# Top.net
KiCad netlist of a schematic drawn in Altium Designer
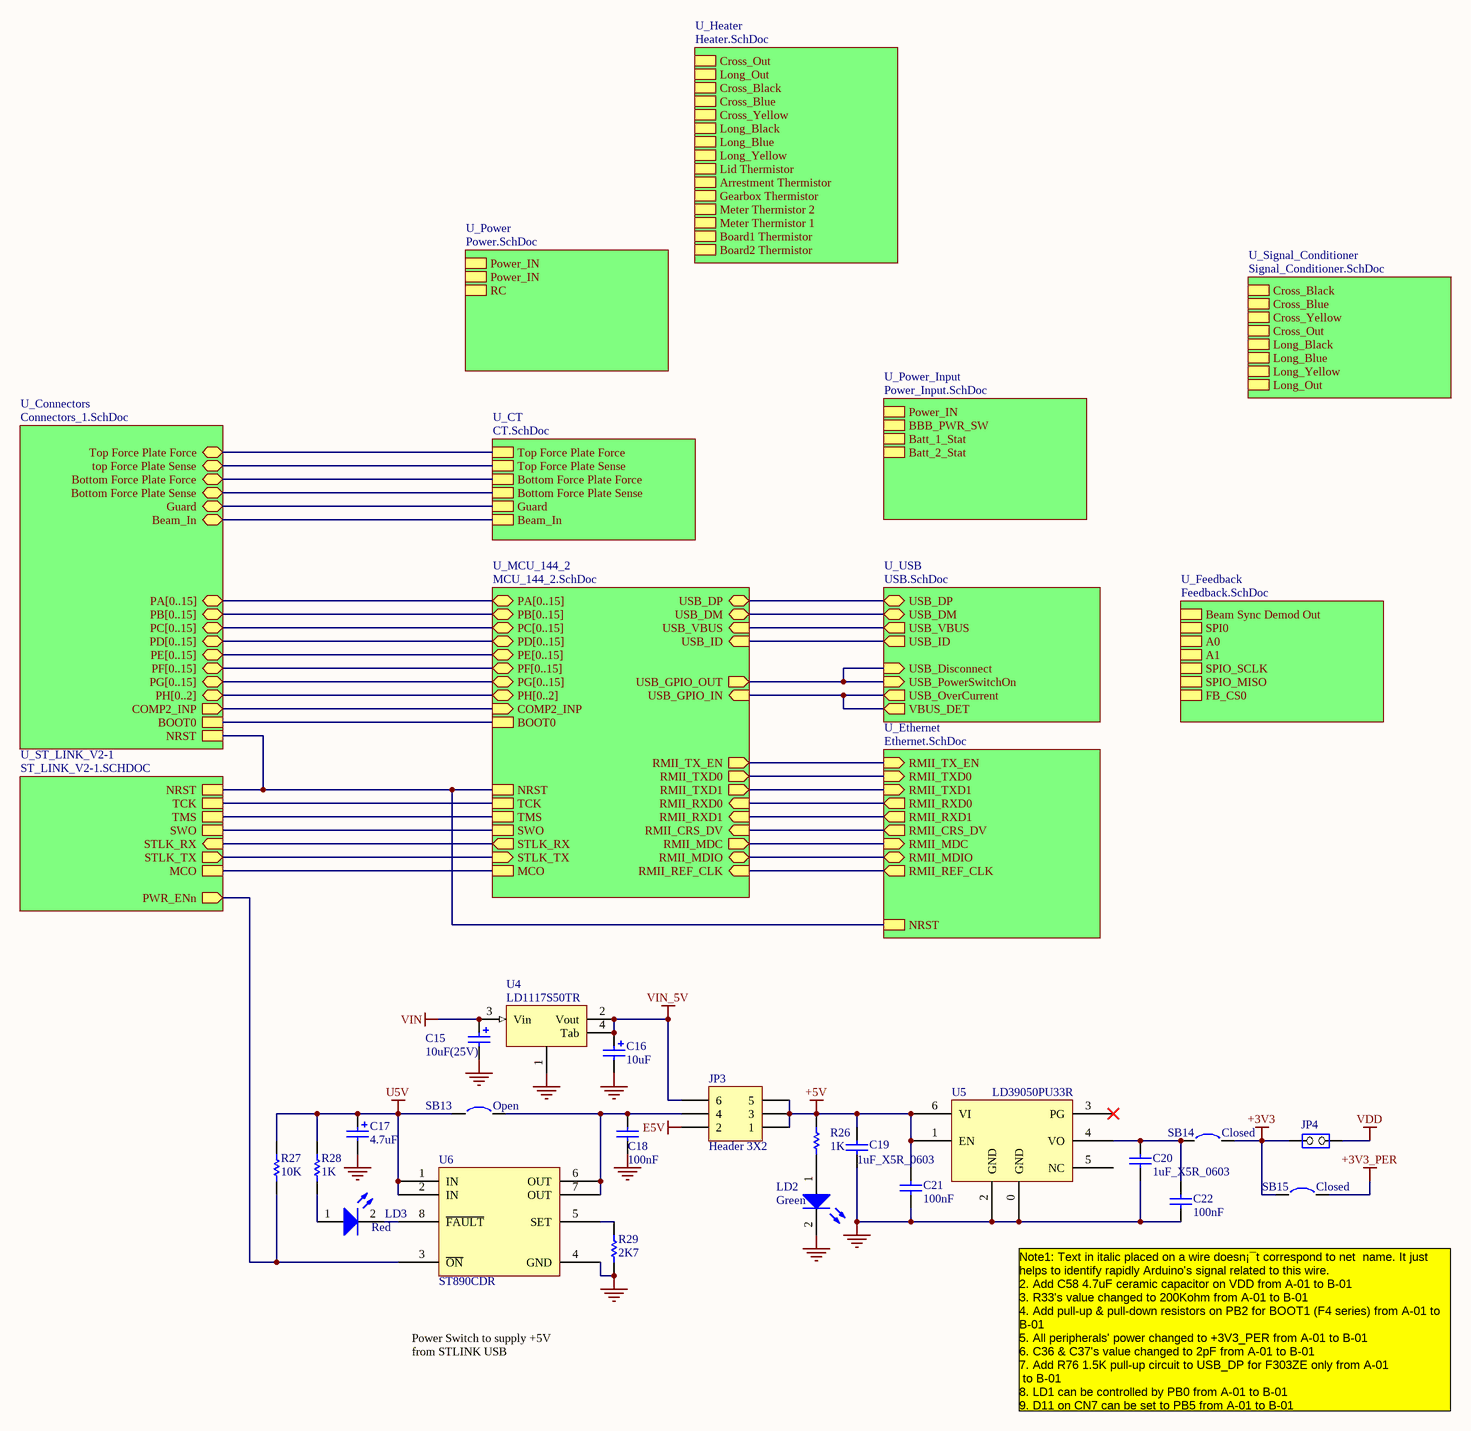
[diagram p0: Top.SchDoc]

(export (version "E")
  (design (tool "Eeschema 10.0.6"))
  (components
    (comp (ref "C15")
      (value "10uF(25V)")
      (footprint "TAN-B")
      (description "Polarized Capacitor (Radial)")
      (fields (field (name "PUBLISHER") "Altium Limited"))
      (libsource (lib "Miscellaneous Devices") (part "Cap Pol1"))
    )
    (comp (ref "C16")
      (value "10uF")
      (footprint "TAN-A")
      (description "Polarized Capacitor (Radial)")
      (fields (field (name "PUBLISHER") "Altium Limited"))
      (libsource (lib "Miscellaneous Devices") (part "Cap Pol1"))
    )
    (comp (ref "C17")
      (value "4.7uF")
      (footprint "TAN-A")
      (description "Polarized Capacitor (Radial)")
      (fields (field (name "PUBLISHER") "Altium Limited"))
      (libsource (lib "*") (part "Cap Pol1"))
    )
    (comp (ref "C18")
      (value "100nF")
      (footprint "0603C")
      (description "Capacitor 0402 / 0603 / 0805")
      (libsource (lib "MCD_TOOLS") (part "Capacitor_ST"))
    )
    (comp (ref "C19")
      (value "1uF_X5R_0603")
      (footprint "0603C")
      (description "0603  X5R 1µF")
      (fields (field (name "TOLERANCE") "10%"))
      (libsource (lib "MB963_1") (part "CAP SMD 0603  X5R 1µF 25V 10%"))
    )
    (comp (ref "C20")
      (value "1uF_X5R_0603")
      (footprint "0603C")
      (description "0603  X5R 1µF")
      (fields (field (name "TOLERANCE") "10%"))
      (libsource (lib "MB963_1") (part "CAP SMD 0603  X5R 1µF 25V 10%"))
    )
    (comp (ref "C21")
      (value "100nF")
      (footprint "0603C")
      (description "Capacitor 0402 / 0603 / 0805")
      (libsource (lib "MCD_TOOLS") (part "Capacitor_ST"))
    )
    (comp (ref "C22")
      (value "100nF")
      (footprint "0603C")
      (description "Capacitor 0402 / 0603 / 0805")
      (libsource (lib "MCD_TOOLS") (part "Capacitor_ST"))
    )
    (comp (ref "JP3")
      (value "Header 3X2")
      (footprint "HDR_3x2_2R54_V_M")
      (description "Header, 3-Pin, Dual row")
      (fields (field (name "PUBLISHER") "Altium Limited"))
      (libsource (lib "Miscellaneous Connectors") (part "Header 3X2"))
    )
    (comp (ref "JP4") (value "~") (footprint "HDR_1x2_2R54_V_M_S") (libsource (lib "*") (part "JP2")))
    (comp (ref "LD2")
      (value "Green")
      (footprint "0603D-G")
      (description "Typical RED, GREEN, YELLOW, AMBER GaAs LED")
      (fields (field (name "PUBLISHER") "Altium Limited"))
      (libsource (lib "") (part "LED2_1"))
    )
    (comp (ref "LD3")
      (value "Red")
      (footprint "0603D-R")
      (description "Typical RED, GREEN, YELLOW, AMBER GaAs LED")
      (fields (field (name "PUBLISHER") "Altium Limited"))
      (libsource (lib "Miscellaneous Devices") (part "LED2"))
    )
    (comp (ref "R26")
      (value "1K")
      (footprint "0603R")
      (description "Resistor 0402 / 0603 / 0805")
      (libsource (lib "MCD_TOOLS") (part "Resistor_ST"))
    )
    (comp (ref "R27")
      (value "10K")
      (footprint "STM-SMEE:0603R")
      (description "Resistor 0402 / 0603 / 0805")
      (libsource (lib "MCD_TOOLS") (part "Resistor_ST"))
    )
    (comp (ref "R28")
      (value "1K")
      (footprint "0603R")
      (description "Resistor")
      (fields (field (name "PUBLISHER") "Altium Limited"))
      (libsource (lib "*") (part "Res1"))
    )
    (comp (ref "R29")
      (value "2K7")
      (footprint "STM-SMEE:0603R")
      (description "Resistor 0402 / 0603 / 0805")
      (libsource (lib "MCD_TOOLS") (part "Resistor_ST"))
    )
    (comp (ref "SB13")
      (value "Open")
      (footprint "SB_0603")
      (description "Circuit Breaker")
      (fields (field (name "PUBLISHER") "Altium Limited"))
      (libsource (lib "MB1167") (part "Circuit Breaker"))
    )
    (comp (ref "SB14")
      (value "Closed")
      (footprint "SB_0603")
      (description "Circuit Breaker")
      (fields (field (name "PUBLISHER") "Altium Limited"))
      (libsource (lib "MB1167") (part "Circuit Breaker_close"))
    )
    (comp (ref "SB15")
      (value "Closed")
      (footprint "SB_0603")
      (description "Circuit Breaker")
      (fields (field (name "PUBLISHER") "Altium Limited"))
      (libsource (lib "MB1167") (part "Circuit Breaker_close"))
    )
    (comp (ref "U4") (value "LD1117S50TR") (footprint "SOT-223") (libsource (lib "MB1137") (part "LD1117")))
    (comp (ref "U5")
      (value "LD39050PU33R")
      (footprint "DFN6_0R95_3x3_TP")
      (libsource (lib "MB1137") (part "LD39050P"))
    )
    (comp (ref "U6")
      (value "ST890CDR")
      (footprint "SOIC8_1R27_4R9X6")
      (libsource (lib "MB1137") (part "ST890CDR"))
    )
  )
  (nets
    (net (code "1") (name "+3V3") (class "Default")
      (node (ref "JP4") (pin "1") (pinfunction "COMMON_1") (pintype "passive"))
      (node (ref "SB14") (pin "2") (pinfunction "2_2") (pintype "passive"))
      (node (ref "SB15") (pin "1") (pinfunction "1_1") (pintype "passive"))
    )
    (net (code "2") (name "+3V3_PER") (class "Default")
      (node (ref "SB15") (pin "2") (pinfunction "2_2") (pintype "passive"))
    )
    (net (code "3") (name "+5V") (class "Default")
      (node (ref "C19") (pin "1") (pinfunction "1_1") (pintype "passive"))
      (node (ref "C21") (pin "2") (pinfunction "2_2") (pintype "passive"))
      (node (ref "JP3") (pin "1") (pinfunction "1_1") (pintype "passive"))
      (node (ref "JP3") (pin "3") (pinfunction "3_3") (pintype "passive"))
      (node (ref "JP3") (pin "5") (pinfunction "5_5") (pintype "passive"))
      (node (ref "R26") (pin "2") (pinfunction "2_2") (pintype "passive"))
      (node (ref "U5") (pin "1") (pinfunction "EN_1") (pintype "passive"))
      (node (ref "U5") (pin "6") (pinfunction "VI_6") (pintype "passive"))
    )
    (net (code "50") (name "/PWR_ENn") (class "Default")
      (node (ref "R27") (pin "2") (pinfunction "2_2") (pintype "passive"))
      (node (ref "U6") (pin "3") (pinfunction "~{ON}_3") (pintype "passive"))
    )
    (net (code "80") (name "E5V") (class "Default")
      (node (ref "JP3") (pin "2") (pinfunction "2_2") (pintype "passive"))
    )
    (net (code "81") (name "GND") (class "Default")
      (node (ref "C15") (pin "2") (pinfunction "2_2") (pintype "passive"))
      (node (ref "C16") (pin "2") (pinfunction "2_2") (pintype "passive"))
      (node (ref "C17") (pin "2") (pinfunction "2_2") (pintype "passive"))
      (node (ref "C18") (pin "1") (pinfunction "1_1") (pintype "passive"))
      (node (ref "C19") (pin "2") (pinfunction "2_2") (pintype "passive"))
      (node (ref "C20") (pin "2") (pinfunction "2_2") (pintype "passive"))
      (node (ref "C21") (pin "1") (pinfunction "1_1") (pintype "passive"))
      (node (ref "C22") (pin "1") (pinfunction "1_1") (pintype "passive"))
      (node (ref "LD2") (pin "2") (pinfunction "K_2") (pintype "passive"))
      (node (ref "R29") (pin "1") (pinfunction "1_1") (pintype "passive"))
      (node (ref "U4") (pin "1") (pintype "passive"))
      (node (ref "U5") (pin "0") (pinfunction "GND_0") (pintype "passive"))
      (node (ref "U5") (pin "2") (pinfunction "GND_2") (pintype "passive"))
      (node (ref "U6") (pin "4") (pinfunction "GND_4") (pintype "passive"))
    )
    (net (code "82") (name "Net-(C18-Pad2)") (class "Default")
      (node (ref "C18") (pin "2") (pinfunction "2_2") (pintype "passive"))
      (node (ref "JP3") (pin "4") (pinfunction "4_4") (pintype "passive"))
      (node (ref "SB13") (pin "2") (pinfunction "2_2") (pintype "passive"))
      (node (ref "U6") (pin "6") (pinfunction "OUT_6") (pintype "passive"))
      (node (ref "U6") (pin "7") (pinfunction "OUT_7") (pintype "passive"))
    )
    (net (code "83") (name "Net-(LD2-A)") (class "Default")
      (node (ref "LD2") (pin "1") (pinfunction "A_1") (pintype "passive"))
      (node (ref "R26") (pin "1") (pinfunction "1_1") (pintype "passive"))
    )
    (net (code "84") (name "Net-(LD3-A)") (class "Default")
      (node (ref "LD3") (pin "1") (pinfunction "A_1") (pintype "passive"))
      (node (ref "R28") (pin "2") (pinfunction "2_2") (pintype "passive"))
    )
    (net (code "85") (name "Net-(LD3-K)") (class "Default")
      (node (ref "LD3") (pin "2") (pinfunction "K_2") (pintype "passive"))
      (node (ref "U6") (pin "8") (pinfunction "~{FAULT}_8") (pintype "passive"))
    )
    (net (code "86") (name "Net-(U5-VO)") (class "Default")
      (node (ref "C20") (pin "1") (pinfunction "1_1") (pintype "passive"))
      (node (ref "C22") (pin "2") (pinfunction "2_2") (pintype "passive"))
      (node (ref "SB14") (pin "1") (pinfunction "1_1") (pintype "passive"))
      (node (ref "U5") (pin "4") (pinfunction "VO_4") (pintype "passive"))
    )
    (net (code "87") (name "Net-(U6-SET)") (class "Default")
      (node (ref "R29") (pin "2") (pinfunction "2_2") (pintype "passive"))
      (node (ref "U6") (pin "5") (pinfunction "SET_5") (pintype "passive"))
    )
    (net (code "88") (name "U5V") (class "Default")
      (node (ref "C17") (pin "1") (pinfunction "1_1") (pintype "passive"))
      (node (ref "R27") (pin "1") (pinfunction "1_1") (pintype "passive"))
      (node (ref "R28") (pin "1") (pinfunction "1_1") (pintype "passive"))
      (node (ref "SB13") (pin "1") (pinfunction "1_1") (pintype "passive"))
      (node (ref "U6") (pin "1") (pinfunction "IN_1") (pintype "passive"))
      (node (ref "U6") (pin "2") (pinfunction "IN_2") (pintype "passive"))
    )
    (net (code "89") (name "VDD") (class "Default")
      (node (ref "JP4") (pin "2") (pinfunction "NO_2") (pintype "passive"))
    )
    (net (code "90") (name "VIN") (class "Default")
      (node (ref "C15") (pin "1") (pinfunction "1_1") (pintype "passive"))
      (node (ref "U4") (pin "3") (pinfunction "Vin_3") (pintype "input"))
    )
    (net (code "91") (name "VIN_5V") (class "Default")
      (node (ref "C16") (pin "1") (pinfunction "1_1") (pintype "passive"))
      (node (ref "JP3") (pin "6") (pinfunction "6_6") (pintype "passive"))
      (node (ref "U4") (pin "2") (pinfunction "Vout_2") (pintype "power_in"))
      (node (ref "U4") (pin "4") (pinfunction "Tab_4") (pintype "power_in"))
    )
    (net (code "92") (name "unconnected-(U5-NC-Pad5)") (class "Default")
      (node (ref "U5") (pin "5") (pinfunction "NC_5") (pintype "passive"))
    )
    (net (code "93") (name "unconnected-(U5-PG-Pad3)") (class "Default")
      (node (ref "U5") (pin "3") (pinfunction "PG_3") (pintype "passive+no_connect"))
    )
  )
)
